# HL_SnapIn_Base.net
KiCad netlist of a schematic drawn in Altium Designer
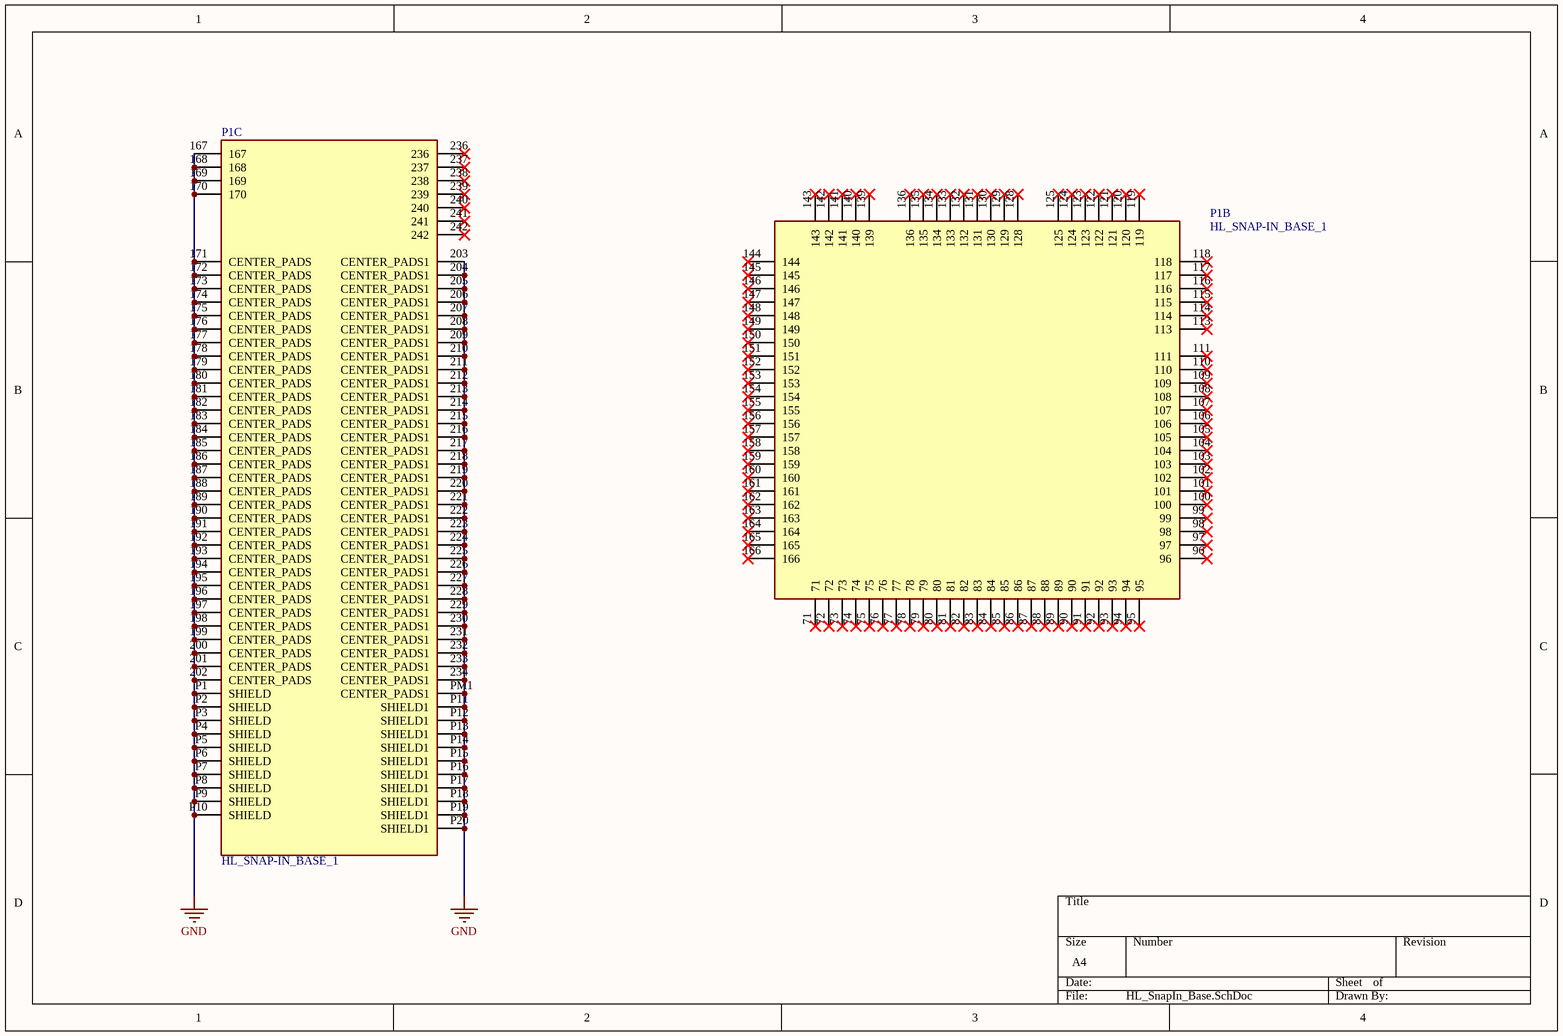
[diagram p0: HL_SnapIn_Base.SchDoc]

(export (version "E")
  (design (tool "Eeschema 10.0.6"))
  (components
    (comp (ref "P1")
      (value "HL_SNAP-IN_BASE_1")
      (footprint "SIERRA_WP_SNAP-IN_BASE")
      (description "WP SNAP IN SOCKET BASE FRAME 157\r\nHL7650")
      (fields (field (name "MF") "Sierra Wireless") (field (name "MP") "WP SNAP-IN BASE"))
      (libsource (lib "Schlib1") (part "HL_SNAP-IN_BASE_1"))
    )
  )
  (nets
    (net (code "1") (name "GND") (class "Default")
      (node (ref "P1") (pin "167") (pinfunction "167_167") (pintype "passive"))
      (node (ref "P1") (pin "168") (pinfunction "168_168") (pintype "passive"))
      (node (ref "P1") (pin "169") (pinfunction "169_169") (pintype "passive"))
      (node (ref "P1") (pin "170") (pinfunction "170_170") (pintype "passive"))
      (node (ref "P1") (pin "171") (pinfunction "CENTER_PADS_171") (pintype "passive"))
      (node (ref "P1") (pin "172") (pinfunction "CENTER_PADS_172") (pintype "passive"))
      (node (ref "P1") (pin "173") (pinfunction "CENTER_PADS_173") (pintype "passive"))
      (node (ref "P1") (pin "174") (pinfunction "CENTER_PADS_174") (pintype "passive"))
      (node (ref "P1") (pin "175") (pinfunction "CENTER_PADS_175") (pintype "passive"))
      (node (ref "P1") (pin "176") (pinfunction "CENTER_PADS_176") (pintype "passive"))
      (node (ref "P1") (pin "177") (pinfunction "CENTER_PADS_177") (pintype "passive"))
      (node (ref "P1") (pin "178") (pinfunction "CENTER_PADS_178") (pintype "passive"))
      (node (ref "P1") (pin "179") (pinfunction "CENTER_PADS_179") (pintype "passive"))
      (node (ref "P1") (pin "180") (pinfunction "CENTER_PADS_180") (pintype "passive"))
      (node (ref "P1") (pin "181") (pinfunction "CENTER_PADS_181") (pintype "passive"))
      (node (ref "P1") (pin "182") (pinfunction "CENTER_PADS_182") (pintype "passive"))
      (node (ref "P1") (pin "183") (pinfunction "CENTER_PADS_183") (pintype "passive"))
      (node (ref "P1") (pin "184") (pinfunction "CENTER_PADS_184") (pintype "passive"))
      (node (ref "P1") (pin "185") (pinfunction "CENTER_PADS_185") (pintype "passive"))
      (node (ref "P1") (pin "186") (pinfunction "CENTER_PADS_186") (pintype "passive"))
      (node (ref "P1") (pin "187") (pinfunction "CENTER_PADS_187") (pintype "passive"))
      (node (ref "P1") (pin "188") (pinfunction "CENTER_PADS_188") (pintype "passive"))
      (node (ref "P1") (pin "189") (pinfunction "CENTER_PADS_189") (pintype "passive"))
      (node (ref "P1") (pin "190") (pinfunction "CENTER_PADS_190") (pintype "passive"))
      (node (ref "P1") (pin "191") (pinfunction "CENTER_PADS_191") (pintype "passive"))
      (node (ref "P1") (pin "192") (pinfunction "CENTER_PADS_192") (pintype "passive"))
      (node (ref "P1") (pin "193") (pinfunction "CENTER_PADS_193") (pintype "passive"))
      (node (ref "P1") (pin "194") (pinfunction "CENTER_PADS_194") (pintype "passive"))
      (node (ref "P1") (pin "195") (pinfunction "CENTER_PADS_195") (pintype "passive"))
      (node (ref "P1") (pin "196") (pinfunction "CENTER_PADS_196") (pintype "passive"))
      (node (ref "P1") (pin "197") (pinfunction "CENTER_PADS_197") (pintype "passive"))
      (node (ref "P1") (pin "198") (pinfunction "CENTER_PADS_198") (pintype "passive"))
      (node (ref "P1") (pin "199") (pinfunction "CENTER_PADS_199") (pintype "passive"))
      (node (ref "P1") (pin "200") (pinfunction "CENTER_PADS_200") (pintype "passive"))
      (node (ref "P1") (pin "201") (pinfunction "CENTER_PADS_201") (pintype "passive"))
      (node (ref "P1") (pin "202") (pinfunction "CENTER_PADS_202") (pintype "passive"))
      (node (ref "P1") (pin "203") (pinfunction "CENTER_PADS1_203") (pintype "passive"))
      (node (ref "P1") (pin "204") (pinfunction "CENTER_PADS1_204") (pintype "passive"))
      (node (ref "P1") (pin "205") (pinfunction "CENTER_PADS1_205") (pintype "passive"))
      (node (ref "P1") (pin "206") (pinfunction "CENTER_PADS1_206") (pintype "passive"))
      (node (ref "P1") (pin "207") (pinfunction "CENTER_PADS1_207") (pintype "passive"))
      (node (ref "P1") (pin "208") (pinfunction "CENTER_PADS1_208") (pintype "passive"))
      (node (ref "P1") (pin "209") (pinfunction "CENTER_PADS1_209") (pintype "passive"))
      (node (ref "P1") (pin "210") (pinfunction "CENTER_PADS1_210") (pintype "passive"))
      (node (ref "P1") (pin "211") (pinfunction "CENTER_PADS1_211") (pintype "passive"))
      (node (ref "P1") (pin "212") (pinfunction "CENTER_PADS1_212") (pintype "passive"))
      (node (ref "P1") (pin "213") (pinfunction "CENTER_PADS1_213") (pintype "passive"))
      (node (ref "P1") (pin "214") (pinfunction "CENTER_PADS1_214") (pintype "passive"))
      (node (ref "P1") (pin "215") (pinfunction "CENTER_PADS1_215") (pintype "passive"))
      (node (ref "P1") (pin "216") (pinfunction "CENTER_PADS1_216") (pintype "passive"))
      (node (ref "P1") (pin "217") (pinfunction "CENTER_PADS1_217") (pintype "passive"))
      (node (ref "P1") (pin "218") (pinfunction "CENTER_PADS1_218") (pintype "passive"))
      (node (ref "P1") (pin "219") (pinfunction "CENTER_PADS1_219") (pintype "passive"))
      (node (ref "P1") (pin "220") (pinfunction "CENTER_PADS1_220") (pintype "passive"))
      (node (ref "P1") (pin "221") (pinfunction "CENTER_PADS1_221") (pintype "passive"))
      (node (ref "P1") (pin "222") (pinfunction "CENTER_PADS1_222") (pintype "passive"))
      (node (ref "P1") (pin "223") (pinfunction "CENTER_PADS1_223") (pintype "passive"))
      (node (ref "P1") (pin "224") (pinfunction "CENTER_PADS1_224") (pintype "passive"))
      (node (ref "P1") (pin "225") (pinfunction "CENTER_PADS1_225") (pintype "passive"))
      (node (ref "P1") (pin "226") (pinfunction "CENTER_PADS1_226") (pintype "passive"))
      (node (ref "P1") (pin "227") (pinfunction "CENTER_PADS1_227") (pintype "passive"))
      (node (ref "P1") (pin "228") (pinfunction "CENTER_PADS1_228") (pintype "passive"))
      (node (ref "P1") (pin "229") (pinfunction "CENTER_PADS1_229") (pintype "passive"))
      (node (ref "P1") (pin "230") (pinfunction "CENTER_PADS1_230") (pintype "passive"))
      (node (ref "P1") (pin "231") (pinfunction "CENTER_PADS1_231") (pintype "passive"))
      (node (ref "P1") (pin "232") (pinfunction "CENTER_PADS1_232") (pintype "passive"))
      (node (ref "P1") (pin "233") (pinfunction "CENTER_PADS1_233") (pintype "passive"))
      (node (ref "P1") (pin "234") (pinfunction "CENTER_PADS1_234") (pintype "passive"))
      (node (ref "P1") (pin "P1") (pinfunction "SHIELD_P1") (pintype "passive"))
      (node (ref "P1") (pin "P10") (pinfunction "SHIELD_P10") (pintype "passive"))
      (node (ref "P1") (pin "P11") (pinfunction "SHIELD1_P11") (pintype "passive"))
      (node (ref "P1") (pin "P12") (pinfunction "SHIELD1_P12") (pintype "passive"))
      (node (ref "P1") (pin "P13") (pinfunction "SHIELD1_P13") (pintype "passive"))
      (node (ref "P1") (pin "P14") (pinfunction "SHIELD1_P14") (pintype "passive"))
      (node (ref "P1") (pin "P15") (pinfunction "SHIELD1_P15") (pintype "passive"))
      (node (ref "P1") (pin "P16") (pinfunction "SHIELD1_P16") (pintype "passive"))
      (node (ref "P1") (pin "P17") (pinfunction "SHIELD1_P17") (pintype "passive"))
      (node (ref "P1") (pin "P18") (pinfunction "SHIELD1_P18") (pintype "passive"))
      (node (ref "P1") (pin "P19") (pinfunction "SHIELD1_P19") (pintype "passive"))
      (node (ref "P1") (pin "P2") (pinfunction "SHIELD_P2") (pintype "passive"))
      (node (ref "P1") (pin "P20") (pinfunction "SHIELD1_P20") (pintype "passive"))
      (node (ref "P1") (pin "P3") (pinfunction "SHIELD_P3") (pintype "passive"))
      (node (ref "P1") (pin "P4") (pinfunction "SHIELD_P4") (pintype "passive"))
      (node (ref "P1") (pin "P5") (pinfunction "SHIELD_P5") (pintype "passive"))
      (node (ref "P1") (pin "P6") (pinfunction "SHIELD_P6") (pintype "passive"))
      (node (ref "P1") (pin "P7") (pinfunction "SHIELD_P7") (pintype "passive"))
      (node (ref "P1") (pin "P8") (pinfunction "SHIELD_P8") (pintype "passive"))
      (node (ref "P1") (pin "P9") (pinfunction "SHIELD_P9") (pintype "passive"))
      (node (ref "P1") (pin "PM1") (pinfunction "CENTER_PADS1_PM1") (pintype "passive"))
    )
    (net (code "2") (name "unconnected-(P1-Pad71)") (class "Default")
      (node (ref "P1") (pin "71") (pinfunction "71_71") (pintype "passive+no_connect"))
    )
    (net (code "3") (name "unconnected-(P1-Pad72)") (class "Default")
      (node (ref "P1") (pin "72") (pinfunction "72_72") (pintype "passive+no_connect"))
    )
    (net (code "4") (name "unconnected-(P1-Pad73)") (class "Default")
      (node (ref "P1") (pin "73") (pinfunction "73_73") (pintype "passive+no_connect"))
    )
    (net (code "5") (name "unconnected-(P1-Pad74)") (class "Default")
      (node (ref "P1") (pin "74") (pinfunction "74_74") (pintype "passive+no_connect"))
    )
    (net (code "6") (name "unconnected-(P1-Pad75)") (class "Default")
      (node (ref "P1") (pin "75") (pinfunction "75_75") (pintype "passive+no_connect"))
    )
    (net (code "7") (name "unconnected-(P1-Pad76)") (class "Default")
      (node (ref "P1") (pin "76") (pinfunction "76_76") (pintype "passive+no_connect"))
    )
    (net (code "8") (name "unconnected-(P1-Pad77)") (class "Default")
      (node (ref "P1") (pin "77") (pinfunction "77_77") (pintype "passive+no_connect"))
    )
    (net (code "9") (name "unconnected-(P1-Pad78)") (class "Default")
      (node (ref "P1") (pin "78") (pinfunction "78_78") (pintype "passive+no_connect"))
    )
    (net (code "10") (name "unconnected-(P1-Pad79)") (class "Default")
      (node (ref "P1") (pin "79") (pinfunction "79_79") (pintype "passive+no_connect"))
    )
    (net (code "11") (name "unconnected-(P1-Pad80)") (class "Default")
      (node (ref "P1") (pin "80") (pinfunction "80_80") (pintype "passive+no_connect"))
    )
    (net (code "12") (name "unconnected-(P1-Pad81)") (class "Default")
      (node (ref "P1") (pin "81") (pinfunction "81_81") (pintype "passive+no_connect"))
    )
    (net (code "13") (name "unconnected-(P1-Pad82)") (class "Default")
      (node (ref "P1") (pin "82") (pinfunction "82_82") (pintype "passive+no_connect"))
    )
    (net (code "14") (name "unconnected-(P1-Pad83)") (class "Default")
      (node (ref "P1") (pin "83") (pinfunction "83_83") (pintype "passive+no_connect"))
    )
    (net (code "15") (name "unconnected-(P1-Pad84)") (class "Default")
      (node (ref "P1") (pin "84") (pinfunction "84_84") (pintype "passive+no_connect"))
    )
    (net (code "16") (name "unconnected-(P1-Pad85)") (class "Default")
      (node (ref "P1") (pin "85") (pinfunction "85_85") (pintype "passive+no_connect"))
    )
    (net (code "17") (name "unconnected-(P1-Pad86)") (class "Default")
      (node (ref "P1") (pin "86") (pinfunction "86_86") (pintype "passive+no_connect"))
    )
    (net (code "18") (name "unconnected-(P1-Pad87)") (class "Default")
      (node (ref "P1") (pin "87") (pinfunction "87_87") (pintype "passive+no_connect"))
    )
    (net (code "19") (name "unconnected-(P1-Pad88)") (class "Default")
      (node (ref "P1") (pin "88") (pinfunction "88_88") (pintype "passive+no_connect"))
    )
    (net (code "20") (name "unconnected-(P1-Pad89)") (class "Default")
      (node (ref "P1") (pin "89") (pinfunction "89_89") (pintype "passive+no_connect"))
    )
    (net (code "21") (name "unconnected-(P1-Pad90)") (class "Default")
      (node (ref "P1") (pin "90") (pinfunction "90_90") (pintype "passive+no_connect"))
    )
    (net (code "22") (name "unconnected-(P1-Pad91)") (class "Default")
      (node (ref "P1") (pin "91") (pinfunction "91_91") (pintype "passive+no_connect"))
    )
    (net (code "23") (name "unconnected-(P1-Pad92)") (class "Default")
      (node (ref "P1") (pin "92") (pinfunction "92_92") (pintype "passive+no_connect"))
    )
    (net (code "24") (name "unconnected-(P1-Pad93)") (class "Default")
      (node (ref "P1") (pin "93") (pinfunction "93_93") (pintype "passive+no_connect"))
    )
    (net (code "25") (name "unconnected-(P1-Pad94)") (class "Default")
      (node (ref "P1") (pin "94") (pinfunction "94_94") (pintype "passive+no_connect"))
    )
    (net (code "26") (name "unconnected-(P1-Pad95)") (class "Default")
      (node (ref "P1") (pin "95") (pinfunction "95_95") (pintype "passive+no_connect"))
    )
    (net (code "27") (name "unconnected-(P1-Pad96)") (class "Default")
      (node (ref "P1") (pin "96") (pinfunction "96_96") (pintype "passive+no_connect"))
    )
    (net (code "28") (name "unconnected-(P1-Pad97)") (class "Default")
      (node (ref "P1") (pin "97") (pinfunction "97_97") (pintype "passive+no_connect"))
    )
    (net (code "29") (name "unconnected-(P1-Pad98)") (class "Default")
      (node (ref "P1") (pin "98") (pinfunction "98_98") (pintype "passive+no_connect"))
    )
    (net (code "30") (name "unconnected-(P1-Pad99)") (class "Default")
      (node (ref "P1") (pin "99") (pinfunction "99_99") (pintype "passive+no_connect"))
    )
    (net (code "31") (name "unconnected-(P1-Pad100)") (class "Default")
      (node (ref "P1") (pin "100") (pinfunction "100_100") (pintype "passive+no_connect"))
    )
    (net (code "32") (name "unconnected-(P1-Pad101)") (class "Default")
      (node (ref "P1") (pin "101") (pinfunction "101_101") (pintype "passive+no_connect"))
    )
    (net (code "33") (name "unconnected-(P1-Pad102)") (class "Default")
      (node (ref "P1") (pin "102") (pinfunction "102_102") (pintype "passive+no_connect"))
    )
    (net (code "34") (name "unconnected-(P1-Pad103)") (class "Default")
      (node (ref "P1") (pin "103") (pinfunction "103_103") (pintype "passive+no_connect"))
    )
    (net (code "35") (name "unconnected-(P1-Pad104)") (class "Default")
      (node (ref "P1") (pin "104") (pinfunction "104_104") (pintype "passive+no_connect"))
    )
    (net (code "36") (name "unconnected-(P1-Pad105)") (class "Default")
      (node (ref "P1") (pin "105") (pinfunction "105_105") (pintype "passive+no_connect"))
    )
    (net (code "37") (name "unconnected-(P1-Pad106)") (class "Default")
      (node (ref "P1") (pin "106") (pinfunction "106_106") (pintype "passive+no_connect"))
    )
    (net (code "38") (name "unconnected-(P1-Pad107)") (class "Default")
      (node (ref "P1") (pin "107") (pinfunction "107_107") (pintype "passive+no_connect"))
    )
    (net (code "39") (name "unconnected-(P1-Pad108)") (class "Default")
      (node (ref "P1") (pin "108") (pinfunction "108_108") (pintype "passive+no_connect"))
    )
    (net (code "40") (name "unconnected-(P1-Pad109)") (class "Default")
      (node (ref "P1") (pin "109") (pinfunction "109_109") (pintype "passive+no_connect"))
    )
    (net (code "41") (name "unconnected-(P1-Pad110)") (class "Default")
      (node (ref "P1") (pin "110") (pinfunction "110_110") (pintype "passive+no_connect"))
    )
    (net (code "42") (name "unconnected-(P1-Pad111)") (class "Default")
      (node (ref "P1") (pin "111") (pinfunction "111_111") (pintype "passive+no_connect"))
    )
    (net (code "43") (name "unconnected-(P1-Pad113)") (class "Default")
      (node (ref "P1") (pin "113") (pinfunction "113_113") (pintype "passive+no_connect"))
    )
    (net (code "44") (name "unconnected-(P1-Pad114)") (class "Default")
      (node (ref "P1") (pin "114") (pinfunction "114_114") (pintype "passive+no_connect"))
    )
    (net (code "45") (name "unconnected-(P1-Pad115)") (class "Default")
      (node (ref "P1") (pin "115") (pinfunction "115_115") (pintype "passive+no_connect"))
    )
    (net (code "46") (name "unconnected-(P1-Pad116)") (class "Default")
      (node (ref "P1") (pin "116") (pinfunction "116_116") (pintype "passive+no_connect"))
    )
    (net (code "47") (name "unconnected-(P1-Pad117)") (class "Default")
      (node (ref "P1") (pin "117") (pinfunction "117_117") (pintype "passive+no_connect"))
    )
    (net (code "48") (name "unconnected-(P1-Pad118)") (class "Default")
      (node (ref "P1") (pin "118") (pinfunction "118_118") (pintype "passive+no_connect"))
    )
    (net (code "49") (name "unconnected-(P1-Pad119)") (class "Default")
      (node (ref "P1") (pin "119") (pinfunction "119_119") (pintype "passive+no_connect"))
    )
    (net (code "50") (name "unconnected-(P1-Pad120)") (class "Default")
      (node (ref "P1") (pin "120") (pinfunction "120_120") (pintype "passive+no_connect"))
    )
    (net (code "51") (name "unconnected-(P1-Pad121)") (class "Default")
      (node (ref "P1") (pin "121") (pinfunction "121_121") (pintype "passive+no_connect"))
    )
    (net (code "52") (name "unconnected-(P1-Pad122)") (class "Default")
      (node (ref "P1") (pin "122") (pinfunction "122_122") (pintype "passive+no_connect"))
    )
    (net (code "53") (name "unconnected-(P1-Pad123)") (class "Default")
      (node (ref "P1") (pin "123") (pinfunction "123_123") (pintype "passive+no_connect"))
    )
    (net (code "54") (name "unconnected-(P1-Pad124)") (class "Default")
      (node (ref "P1") (pin "124") (pinfunction "124_124") (pintype "passive+no_connect"))
    )
    (net (code "55") (name "unconnected-(P1-Pad125)") (class "Default")
      (node (ref "P1") (pin "125") (pinfunction "125_125") (pintype "passive+no_connect"))
    )
    (net (code "56") (name "unconnected-(P1-Pad128)") (class "Default")
      (node (ref "P1") (pin "128") (pinfunction "128_128") (pintype "passive+no_connect"))
    )
    (net (code "57") (name "unconnected-(P1-Pad129)") (class "Default")
      (node (ref "P1") (pin "129") (pinfunction "129_129") (pintype "passive+no_connect"))
    )
    (net (code "58") (name "unconnected-(P1-Pad130)") (class "Default")
      (node (ref "P1") (pin "130") (pinfunction "130_130") (pintype "passive+no_connect"))
    )
    (net (code "59") (name "unconnected-(P1-Pad131)") (class "Default")
      (node (ref "P1") (pin "131") (pinfunction "131_131") (pintype "passive+no_connect"))
    )
    (net (code "60") (name "unconnected-(P1-Pad132)") (class "Default")
      (node (ref "P1") (pin "132") (pinfunction "132_132") (pintype "passive+no_connect"))
    )
    (net (code "61") (name "unconnected-(P1-Pad133)") (class "Default")
      (node (ref "P1") (pin "133") (pinfunction "133_133") (pintype "passive+no_connect"))
    )
    (net (code "62") (name "unconnected-(P1-Pad134)") (class "Default")
      (node (ref "P1") (pin "134") (pinfunction "134_134") (pintype "passive+no_connect"))
    )
    (net (code "63") (name "unconnected-(P1-Pad135)") (class "Default")
      (node (ref "P1") (pin "135") (pinfunction "135_135") (pintype "passive+no_connect"))
    )
    (net (code "64") (name "unconnected-(P1-Pad136)") (class "Default")
      (node (ref "P1") (pin "136") (pinfunction "136_136") (pintype "passive+no_connect"))
    )
    (net (code "65") (name "unconnected-(P1-Pad139)") (class "Default")
      (node (ref "P1") (pin "139") (pinfunction "139_139") (pintype "passive+no_connect"))
    )
    (net (code "66") (name "unconnected-(P1-Pad140)") (class "Default")
      (node (ref "P1") (pin "140") (pinfunction "140_140") (pintype "passive+no_connect"))
    )
    (net (code "67") (name "unconnected-(P1-Pad141)") (class "Default")
      (node (ref "P1") (pin "141") (pinfunction "141_141") (pintype "passive+no_connect"))
    )
    (net (code "68") (name "unconnected-(P1-Pad142)") (class "Default")
      (node (ref "P1") (pin "142") (pinfunction "142_142") (pintype "passive+no_connect"))
    )
    (net (code "69") (name "unconnected-(P1-Pad143)") (class "Default")
      (node (ref "P1") (pin "143") (pinfunction "143_143") (pintype "passive+no_connect"))
    )
    (net (code "70") (name "unconnected-(P1-Pad144)") (class "Default")
      (node (ref "P1") (pin "144") (pinfunction "144_144") (pintype "passive+no_connect"))
    )
    (net (code "71") (name "unconnected-(P1-Pad145)") (class "Default")
      (node (ref "P1") (pin "145") (pinfunction "145_145") (pintype "passive+no_connect"))
    )
    (net (code "72") (name "unconnected-(P1-Pad146)") (class "Default")
      (node (ref "P1") (pin "146") (pinfunction "146_146") (pintype "passive+no_connect"))
    )
    (net (code "73") (name "unconnected-(P1-Pad147)") (class "Default")
      (node (ref "P1") (pin "147") (pinfunction "147_147") (pintype "passive+no_connect"))
    )
    (net (code "74") (name "unconnected-(P1-Pad148)") (class "Default")
      (node (ref "P1") (pin "148") (pinfunction "148_148") (pintype "passive+no_connect"))
    )
    (net (code "75") (name "unconnected-(P1-Pad149)") (class "Default")
      (node (ref "P1") (pin "149") (pinfunction "149_149") (pintype "passive+no_connect"))
    )
    (net (code "76") (name "unconnected-(P1-Pad150)") (class "Default")
      (node (ref "P1") (pin "150") (pinfunction "150_150") (pintype "passive+no_connect"))
    )
    (net (code "77") (name "unconnected-(P1-Pad151)") (class "Default")
      (node (ref "P1") (pin "151") (pinfunction "151_151") (pintype "passive+no_connect"))
    )
    (net (code "78") (name "unconnected-(P1-Pad152)") (class "Default")
      (node (ref "P1") (pin "152") (pinfunction "152_152") (pintype "passive+no_connect"))
    )
    (net (code "79") (name "unconnected-(P1-Pad153)") (class "Default")
      (node (ref "P1") (pin "153") (pinfunction "153_153") (pintype "passive+no_connect"))
    )
    (net (code "80") (name "unconnected-(P1-Pad154)") (class "Default")
      (node (ref "P1") (pin "154") (pinfunction "154_154") (pintype "passive+no_connect"))
    )
    (net (code "81") (name "unconnected-(P1-Pad155)") (class "Default")
      (node (ref "P1") (pin "155") (pinfunction "155_155") (pintype "passive+no_connect"))
    )
    (net (code "82") (name "unconnected-(P1-Pad156)") (class "Default")
      (node (ref "P1") (pin "156") (pinfunction "156_156") (pintype "passive+no_connect"))
    )
    (net (code "83") (name "unconnected-(P1-Pad157)") (class "Default")
      (node (ref "P1") (pin "157") (pinfunction "157_157") (pintype "passive+no_connect"))
    )
    (net (code "84") (name "unconnected-(P1-Pad158)") (class "Default")
      (node (ref "P1") (pin "158") (pinfunction "158_158") (pintype "passive+no_connect"))
    )
    (net (code "85") (name "unconnected-(P1-Pad159)") (class "Default")
      (node (ref "P1") (pin "159") (pinfunction "159_159") (pintype "passive+no_connect"))
    )
    (net (code "86") (name "unconnected-(P1-Pad160)") (class "Default")
      (node (ref "P1") (pin "160") (pinfunction "160_160") (pintype "passive+no_connect"))
    )
    (net (code "87") (name "unconnected-(P1-Pad161)") (class "Default")
      (node (ref "P1") (pin "161") (pinfunction "161_161") (pintype "passive+no_connect"))
    )
    (net (code "88") (name "unconnected-(P1-Pad162)") (class "Default")
      (node (ref "P1") (pin "162") (pinfunction "162_162") (pintype "passive+no_connect"))
    )
    (net (code "89") (name "unconnected-(P1-Pad163)") (class "Default")
      (node (ref "P1") (pin "163") (pinfunction "163_163") (pintype "passive+no_connect"))
    )
    (net (code "90") (name "unconnected-(P1-Pad164)") (class "Default")
      (node (ref "P1") (pin "164") (pinfunction "164_164") (pintype "passive+no_connect"))
    )
    (net (code "91") (name "unconnected-(P1-Pad165)") (class "Default")
      (node (ref "P1") (pin "165") (pinfunction "165_165") (pintype "passive+no_connect"))
    )
    (net (code "92") (name "unconnected-(P1-Pad166)") (class "Default")
      (node (ref "P1") (pin "166") (pinfunction "166_166") (pintype "passive+no_connect"))
    )
    (net (code "93") (name "unconnected-(P1-Pad236)") (class "Default")
      (node (ref "P1") (pin "236") (pinfunction "236_236") (pintype "passive+no_connect"))
    )
    (net (code "94") (name "unconnected-(P1-Pad237)") (class "Default")
      (node (ref "P1") (pin "237") (pinfunction "237_237") (pintype "passive+no_connect"))
    )
    (net (code "95") (name "unconnected-(P1-Pad238)") (class "Default")
      (node (ref "P1") (pin "238") (pinfunction "238_238") (pintype "passive+no_connect"))
    )
    (net (code "96") (name "unconnected-(P1-Pad239)") (class "Default")
      (node (ref "P1") (pin "239") (pinfunction "239_239") (pintype "passive+no_connect"))
    )
    (net (code "97") (name "unconnected-(P1-Pad240)") (class "Default")
      (node (ref "P1") (pin "240") (pinfunction "240_240") (pintype "passive+no_connect"))
    )
    (net (code "98") (name "unconnected-(P1-Pad241)") (class "Default")
      (node (ref "P1") (pin "241") (pinfunction "241_241") (pintype "passive+no_connect"))
    )
    (net (code "99") (name "unconnected-(P1-Pad242)") (class "Default")
      (node (ref "P1") (pin "242") (pinfunction "242_242") (pintype "passive+no_connect"))
    )
  )
)
